# dac.net
KiCad netlist of a schematic drawn in Altium Designer
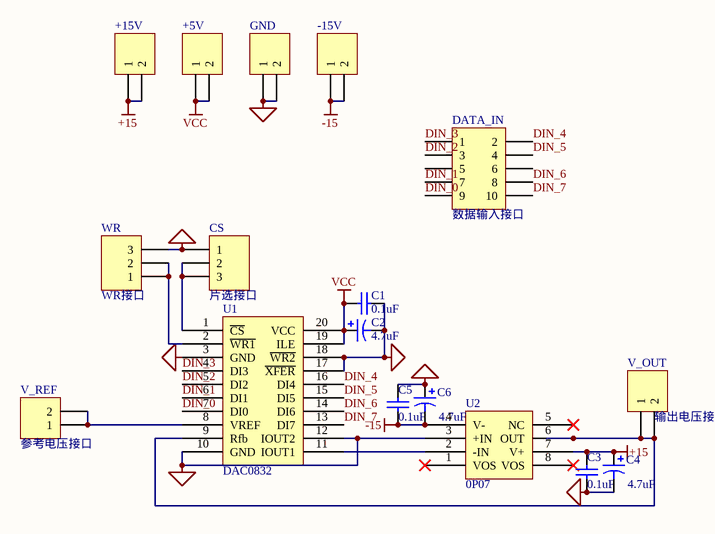
[diagram p0: dac.SchDoc]

(export (version "E")
  (design (tool "Eeschema 10.0.6"))
  (components
    (comp (ref "+5V")
      (value "+5V")
      (footprint "HDR1X2")
      (description "Header, 2-Pin, Right Angle")
      (fields (field (name "PUBLISHER") "Altium Limited"))
      (libsource (lib "") (part "Header 2H_1"))
    )
    (comp (ref "+15V")
      (value "+15V")
      (footprint "HDR1X2")
      (description "Header, 2-Pin, Right Angle")
      (fields (field (name "PUBLISHER") "Altium Limited"))
      (libsource (lib "") (part "Header 2H_1"))
    )
    (comp (ref "-15V")
      (value "-15V")
      (footprint "HDR1X2")
      (description "Header, 2-Pin, Right Angle")
      (fields (field (name "PUBLISHER") "Altium Limited"))
      (libsource (lib "") (part "Header 2H_1"))
    )
    (comp (ref "C1")
      (value "0.1uF")
      (footprint "C0805")
      (description "Capacitor")
      (fields (field (name "Comment") "Cap") (field (name "PUBLISHER") "Altium Limited"))
      (libsource (lib "Miscellaneous Devices") (part "Cap"))
    )
    (comp (ref "C2")
      (value "4.7uF")
      (footprint "C1206")
      (description "Polarized Capacitor (Radial)")
      (fields (field (name "Comment") "Cap Pol1") (field (name "PUBLISHER") "Altium Limited"))
      (libsource (lib "Miscellaneous Devices") (part "Cap Pol1"))
    )
    (comp (ref "C3")
      (value "0.1uF")
      (footprint "C0805")
      (description "Capacitor")
      (fields (field (name "Comment") "Cap") (field (name "PUBLISHER") "Altium Limited"))
      (libsource (lib "Miscellaneous Devices") (part "Cap"))
    )
    (comp (ref "C4")
      (value "4.7uF")
      (footprint "C1206")
      (description "Polarized Capacitor (Radial)")
      (fields (field (name "Comment") "Cap Pol1") (field (name "PUBLISHER") "Altium Limited"))
      (libsource (lib "Miscellaneous Devices") (part "Cap Pol1"))
    )
    (comp (ref "C5")
      (value "0.1uF")
      (footprint "C0805")
      (description "Capacitor")
      (fields (field (name "Comment") "Cap") (field (name "PUBLISHER") "Altium Limited"))
      (libsource (lib "Miscellaneous Devices") (part "Cap"))
    )
    (comp (ref "C6")
      (value "4.7uF")
      (footprint "C1206")
      (description "Polarized Capacitor (Radial)")
      (fields (field (name "Comment") "Cap Pol1") (field (name "PUBLISHER") "Altium Limited"))
      (libsource (lib "Miscellaneous Devices") (part "Cap Pol1"))
    )
    (comp (ref "CS")
      (value "片选接口")
      (footprint "HDR1X3")
      (description "Header, 3-Pin, Right Angle")
      (fields (field (name "PUBLISHER") "Altium Limited"))
      (libsource (lib "") (part "Header 3H_1"))
    )
    (comp (ref "DATA_IN")
      (value "数据输入接口")
      (footprint "HDR2X5")
      (description "Header, 5-Pin, Dual row")
      (fields (field (name "PUBLISHER") "Altium Limited"))
      (libsource (lib "自定义库") (part "Header 5X2"))
    )
    (comp (ref "GND")
      (value "GND")
      (footprint "HDR1X2")
      (description "Header, 2-Pin, Right Angle")
      (fields (field (name "PUBLISHER") "Altium Limited"))
      (libsource (lib "") (part "Header 2H_1"))
    )
    (comp (ref "U1") (value "DAC0832") (footprint "DIP-20") (libsource (lib "自定义库") (part "DAC0832")))
    (comp (ref "U2") (value "0P07") (footprint "DIP-8") (libsource (lib "自定义库") (part "OP07")))
    (comp (ref "V_OUT")
      (value "输出电压接口")
      (footprint "HDR1X2")
      (description "Header, 2-Pin, Right Angle")
      (fields (field (name "PUBLISHER") "Altium Limited"))
      (libsource (lib "") (part "Header 2H_1"))
    )
    (comp (ref "V_REF")
      (value "参考电压接口")
      (footprint "HDR1X2")
      (description "Header, 2-Pin, Right Angle")
      (fields (field (name "PUBLISHER") "Altium Limited"))
      (libsource (lib "自定义库") (part "Header 2H"))
    )
    (comp (ref "WR")
      (value "WR接口")
      (footprint "HDR1X3")
      (description "Header, 3-Pin, Right Angle")
      (fields (field (name "PUBLISHER") "Altium Limited"))
      (libsource (lib "自定义库") (part "Header 3H"))
    )
  )
  (nets
    (net (code "1") (name "+15") (class "Default")
      (node (ref "+15V") (pin "1") (pinfunction "1_1") (pintype "passive"))
      (node (ref "+15V") (pin "2") (pinfunction "2_2") (pintype "passive"))
      (node (ref "C3") (pin "2") (pinfunction "2_2") (pintype "passive"))
      (node (ref "C4") (pin "1") (pinfunction "1_1") (pintype "passive"))
      (node (ref "U2") (pin "7") (pinfunction "V+_7") (pintype "passive"))
    )
    (net (code "2") (name "-15") (class "Default")
      (node (ref "-15V") (pin "1") (pinfunction "1_1") (pintype "passive"))
      (node (ref "-15V") (pin "2") (pinfunction "2_2") (pintype "passive"))
      (node (ref "C5") (pin "1") (pinfunction "1_1") (pintype "passive"))
      (node (ref "C6") (pin "2") (pinfunction "2_2") (pintype "passive"))
      (node (ref "U2") (pin "4") (pinfunction "V-_4") (pintype "passive"))
    )
    (net (code "3") (name "/DIN_0") (class "Default")
      (node (ref "DATA_IN") (pin "9") (pinfunction "9_9") (pintype "passive"))
      (node (ref "U1") (pin "7") (pinfunction "DI0_7") (pintype "passive"))
    )
    (net (code "4") (name "/DIN_1") (class "Default")
      (node (ref "DATA_IN") (pin "7") (pinfunction "7_7") (pintype "passive"))
      (node (ref "U1") (pin "6") (pinfunction "DI1_6") (pintype "passive"))
    )
    (net (code "5") (name "/DIN_2") (class "Default")
      (node (ref "DATA_IN") (pin "3") (pinfunction "3_3") (pintype "passive"))
      (node (ref "U1") (pin "5") (pinfunction "DI2_5") (pintype "passive"))
    )
    (net (code "6") (name "/DIN_3") (class "Default")
      (node (ref "DATA_IN") (pin "1") (pinfunction "1_1") (pintype "passive"))
      (node (ref "U1") (pin "4") (pinfunction "DI3_4") (pintype "passive"))
    )
    (net (code "7") (name "/DIN_4") (class "Default")
      (node (ref "DATA_IN") (pin "2") (pinfunction "2_2") (pintype "passive"))
      (node (ref "U1") (pin "16") (pinfunction "DI4_16") (pintype "passive"))
    )
    (net (code "8") (name "/DIN_5") (class "Default")
      (node (ref "DATA_IN") (pin "4") (pinfunction "4_4") (pintype "passive"))
      (node (ref "U1") (pin "15") (pinfunction "DI5_15") (pintype "passive"))
    )
    (net (code "9") (name "/DIN_6") (class "Default")
      (node (ref "DATA_IN") (pin "8") (pinfunction "8_8") (pintype "passive"))
      (node (ref "U1") (pin "14") (pinfunction "DI6_14") (pintype "passive"))
    )
    (net (code "10") (name "/DIN_7") (class "Default")
      (node (ref "DATA_IN") (pin "10") (pinfunction "10_10") (pintype "passive"))
      (node (ref "U1") (pin "13") (pinfunction "DI7_13") (pintype "passive"))
    )
    (net (code "11") (name "GND") (class "Default")
      (node (ref "C1") (pin "2") (pinfunction "2_2") (pintype "passive"))
      (node (ref "C2") (pin "2") (pinfunction "2_2") (pintype "passive"))
      (node (ref "C3") (pin "1") (pinfunction "1_1") (pintype "passive"))
      (node (ref "C4") (pin "2") (pinfunction "2_2") (pintype "passive"))
      (node (ref "C5") (pin "2") (pinfunction "2_2") (pintype "passive"))
      (node (ref "C6") (pin "1") (pinfunction "1_1") (pintype "passive"))
      (node (ref "CS") (pin "1") (pinfunction "1_1") (pintype "passive"))
      (node (ref "GND") (pin "1") (pinfunction "1_1") (pintype "passive"))
      (node (ref "GND") (pin "2") (pinfunction "2_2") (pintype "passive"))
      (node (ref "U1") (pin "10") (pinfunction "GND_10") (pintype "passive"))
      (node (ref "U1") (pin "12") (pinfunction "IOUT2_12") (pintype "passive"))
      (node (ref "U1") (pin "17") (pinfunction "~{XFER}_17") (pintype "passive"))
      (node (ref "U1") (pin "18") (pinfunction "~{WR2}_18") (pintype "passive"))
      (node (ref "U1") (pin "3") (pinfunction "GND_3") (pintype "passive"))
      (node (ref "U2") (pin "3") (pinfunction "+IN_3") (pintype "passive"))
      (node (ref "WR") (pin "3") (pinfunction "3_3") (pintype "passive"))
    )
    (net (code "12") (name "Net-(U1-IOUT1)") (class "Default")
      (node (ref "U1") (pin "11") (pinfunction "IOUT1_11") (pintype "passive"))
      (node (ref "U2") (pin "2") (pinfunction "-IN_2") (pintype "passive"))
    )
    (net (code "13") (name "Net-(U1-Rfb)") (class "Default")
      (node (ref "U1") (pin "9") (pinfunction "Rfb_9") (pintype "passive"))
      (node (ref "U2") (pin "6") (pinfunction "OUT_6") (pintype "passive"))
      (node (ref "V_OUT") (pin "1") (pinfunction "1_1") (pintype "passive"))
      (node (ref "V_OUT") (pin "2") (pinfunction "2_2") (pintype "passive"))
    )
    (net (code "14") (name "Net-(U1-VREF)") (class "Default")
      (node (ref "U1") (pin "8") (pinfunction "VREF_8") (pintype "passive"))
      (node (ref "V_REF") (pin "1") (pinfunction "1_1") (pintype "passive"))
      (node (ref "V_REF") (pin "2") (pinfunction "2_2") (pintype "passive"))
    )
    (net (code "15") (name "Net-(U1-~{CS})") (class "Default")
      (node (ref "CS") (pin "2") (pinfunction "2_2") (pintype "passive"))
      (node (ref "CS") (pin "3") (pinfunction "3_3") (pintype "passive"))
      (node (ref "U1") (pin "1") (pinfunction "~{CS}_1") (pintype "passive"))
    )
    (net (code "16") (name "Net-(U1-~{WR1})") (class "Default")
      (node (ref "U1") (pin "2") (pinfunction "~{WR1}_2") (pintype "passive"))
      (node (ref "WR") (pin "1") (pinfunction "1_1") (pintype "passive"))
      (node (ref "WR") (pin "2") (pinfunction "2_2") (pintype "passive"))
    )
    (net (code "17") (name "VCC") (class "Default")
      (node (ref "+5V") (pin "1") (pinfunction "1_1") (pintype "passive"))
      (node (ref "+5V") (pin "2") (pinfunction "2_2") (pintype "passive"))
      (node (ref "C1") (pin "1") (pinfunction "1_1") (pintype "passive"))
      (node (ref "C2") (pin "1") (pinfunction "1_1") (pintype "passive"))
      (node (ref "U1") (pin "19") (pinfunction "ILE_19") (pintype "passive"))
      (node (ref "U1") (pin "20") (pinfunction "VCC_20") (pintype "passive"))
    )
    (net (code "18") (name "unconnected-(DATA_IN-Pad5)") (class "Default")
      (node (ref "DATA_IN") (pin "5") (pinfunction "5_5") (pintype "passive"))
    )
    (net (code "19") (name "unconnected-(DATA_IN-Pad6)") (class "Default")
      (node (ref "DATA_IN") (pin "6") (pinfunction "6_6") (pintype "passive"))
    )
    (net (code "20") (name "unconnected-(U2-NC-Pad5)") (class "Default")
      (node (ref "U2") (pin "5") (pinfunction "NC_5") (pintype "passive+no_connect"))
    )
    (net (code "21") (name "unconnected-(U2-VOS-Pad1)") (class "Default")
      (node (ref "U2") (pin "1") (pinfunction "VOS_1") (pintype "passive+no_connect"))
    )
    (net (code "22") (name "unconnected-(U2-VOS-Pad8)") (class "Default")
      (node (ref "U2") (pin "8") (pinfunction "VOS_8") (pintype "passive+no_connect"))
    )
  )
)
